# Power_Converter_Circuit.net
KiCad netlist of a schematic drawn in Altium Designer
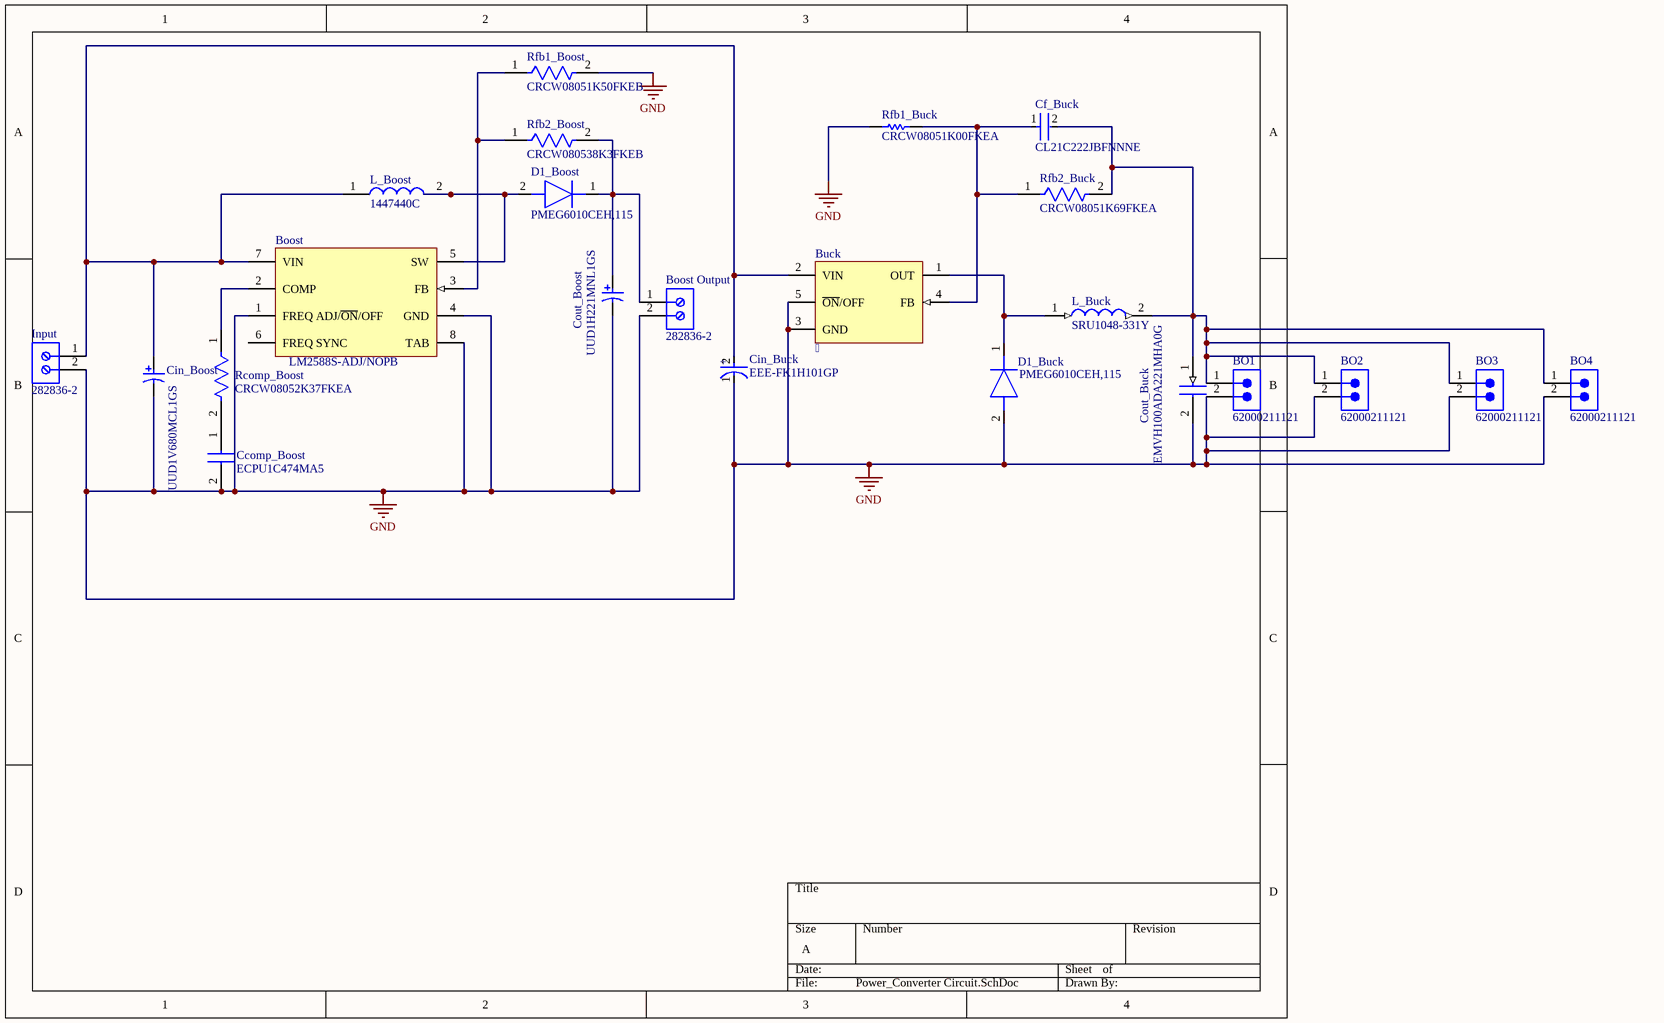
[diagram p0: Power_Converter Circuit.SchDoc]

(export (version "E")
  (design (tool "Eeschema 10.0.6"))
  (components
    (comp (ref "BO1")
      (value "62000211121")
      (footprint "62000211121")
      (libsource (lib "Altium Content Vault") (part "Header_Male_1R_02P"))
    )
    (comp (ref "BO2")
      (value "62000211121")
      (footprint "62000211121")
      (libsource (lib "Altium Content Vault") (part "Header_Male_1R_02P"))
    )
    (comp (ref "BO3")
      (value "62000211121")
      (footprint "62000211121")
      (libsource (lib "Altium Content Vault") (part "Header_Male_1R_02P"))
    )
    (comp (ref "BO4")
      (value "62000211121")
      (footprint "62000211121")
      (libsource (lib "Altium Content Vault") (part "Header_Male_1R_02P"))
    )
    (comp (ref "Boost")
      (value "LM2588S-ADJ/NOPB")
      (footprint "KTW0007B_N")
      (description "SIMPLE SWITCHER® 5A Flyback Regulator with Shutdown, 7-pin TO-263, Pb-Free")
      (fields (field (name "MANUFACTURER") "Texas Instruments"))
      (libsource (lib "Altium Content Vault") (part "PM-SWREG-LM2586S-12"))
    )
    (comp (ref "Boost Output")
      (value "282836-2")
      (footprint "TECO-282836-2_V")
      (description "Female Header, Pitch 5 mm, 1 x 2 Position, Height 10 mm, Tail Length 3.5 mm, Rohs, Bulk")
      (fields (field (name "VOLTAGE") "300V") (field (name "MANUFACTURER") "TE Connectivity"))
      (libsource (lib "Altium Content Vault") (part "CN-1P-F-TB2"))
    )
    (comp (ref "Buck")
      (value "")
      (footprint "NDH0005A")
      (description "SIMPLE SWITCHER® Power Converter 150 KHz 1A Step-Down Voltage Regulator, 5-pin TO-220, Pb-Free")
      (fields (field (name "MANUFACTURER") "Texas Instruments"))
      (libsource (lib "Altium Content Vault") (part "PM-REG-LM2595T-12"))
    )
    (comp (ref "Ccomp_Boost")
      (value "ECPU1C474MA5")
      (footprint "SamacSys:ECPU1C154MA5")
      (description "Capacitor")
      (libsource (lib "*") (part "ECPU1C474MA5"))
    )
    (comp (ref "Cf_Buck")
      (value "CL21C222JBFNNNE")
      (footprint "FP-CL21-IPC_C")
      (description "CL21 Series 0805 2.2nF 50V ±5% Tolerance C0G Multilayer Ceramic Chip Capacitor")
      (fields (field (name "TOLERANCE") "5%") (field (name "VOLTAGE") "50V"))
      (libsource (lib "Altium Content Vault") (part "b4654b650e69147ec39a6b967a45e02"))
    )
    (comp (ref "Cin_Boost")
      (value "UUD1V680MCL1GS")
      (footprint "NIC-CAPA2-6.3X7.7_V")
      (fields (field (name "MANUFACTURER") "Nichicon"))
      (libsource (lib "Altium Content Vault") (part "NIC-CAP-P-2"))
    )
    (comp (ref "Cin_Buck")
      (value "EEE-FK1H101GP")
      (footprint "FP-FKF-MFG")
      (description "CAP ALUM 100UF 20% 50V SMD")
      (fields (field (name "VOLTAGE") "50V") (field (name "TOLERANCE") "20%"))
      (libsource (lib "Altium Content Vault") (part "203bc49f2ac43e59fd269a8c329ed05"))
    )
    (comp (ref "Cout_Boost")
      (value "UUD1H221MNL1GS")
      (footprint "NIC-CAPA2-10X10_V")
      (fields (field (name "MANUFACTURER") "Nichicon"))
      (libsource (lib "Altium Content Vault") (part "NIC-CAP-P-2"))
    )
    (comp (ref "Cout_Buck")
      (value "EMVH100ADA221MHA0G")
      (footprint "SamacSys:CAPAE830X1050N")
      (description "Capacitor")
      (libsource (lib "*") (part "EMVH100ADA221MHA0G"))
    )
    (comp (ref "D1_Boost")
      (value "PMEG6010CEH,115")
      (footprint "SamacSys:SODFL3516X120N")
      (description "Diode")
      (fields (field (name "MOUSER PART NUMBER") "771-PMEG6010CEH-T/R"))
      (libsource (lib "*") (part "PMEG6010CEH,115"))
    )
    (comp (ref "D1_Buck")
      (value "PMEG6010CEH,115")
      (footprint "SamacSys:SODFL3516X120N")
      (description "Diode")
      (fields (field (name "MOUSER PART NUMBER") "771-PMEG6010CEH-T/R"))
      (libsource (lib "*") (part "PMEG6010CEH,115"))
    )
    (comp (ref "Input")
      (value "282836-2")
      (footprint "TECO-282836-2_V")
      (description "Female Header, Pitch 5 mm, 1 x 2 Position, Height 10 mm, Tail Length 3.5 mm, Rohs, Bulk")
      (fields (field (name "VOLTAGE") "300V") (field (name "MANUFACTURER") "TE Connectivity"))
      (libsource (lib "Altium Content Vault") (part "CN-1P-F-TB2"))
    )
    (comp (ref "L_Boost")
      (value "1447440C")
      (footprint "SamacSys:1447440C")
      (description "Inductor")
      (fields (field (name "MOUSER PART NUMBER") "580-1447440C"))
      (libsource (lib "*") (part "1447440C"))
    )
    (comp (ref "L_Buck")
      (value "SRU1048-331Y")
      (footprint "SamacSys:INDPM100100X510N")
      (description "Inductor")
      (libsource (lib "*") (part "SRU1048-331Y"))
    )
    (comp (ref "Rcomp_Boost")
      (value "CRCW08052K37FKEA")
      (footprint "FP-CRCW0805-e3-IPC_C")
      (description "RES Thick Film, 2.37kΩ, 1%, 0.125W, 100ppm/°C, 0805")
      (fields (field (name "TOLERANCE") "1%"))
      (libsource (lib "Altium Content Vault") (part "1029c3af85768c4190bb7ad29bc67b5"))
    )
    (comp (ref "Rfb1_Boost")
      (value "CRCW08051K50FKEB")
      (footprint "FP-CRCW0805-e3-IPC_C")
      (description "RES Thick Film, 1.5kΩ, 1%, 0.125W, 100ppm/°C, 0805")
      (fields (field (name "TOLERANCE") "1%"))
      (libsource (lib "Altium Content Vault") (part "1029c3af85768c4190bb7ad29bc67b5"))
    )
    (comp (ref "Rfb1_Buck")
      (value "CRCW08051K00FKEA")
      (footprint "RESC2013X50X30NL20T20")
      (fields (field (name "MANUFACTURER") "Vishay Dale"))
      (libsource (lib "Altium Content Vault") (part "RES"))
    )
    (comp (ref "Rfb2_Boost")
      (value "CRCW080538K3FKEB")
      (footprint "FP-CRCW0805-e3-MFG")
      (description "RES Thick Film, 38.3kΩ, 1%, 0.125W, 100ppm/°C, 0805")
      (fields (field (name "TOLERANCE") "1%"))
      (libsource (lib "Altium Content Vault") (part "1029c3af85768c4190bb7ad29bc67b5"))
    )
    (comp (ref "Rfb2_Buck")
      (value "CRCW08051K69FKEA")
      (footprint "FP-CRCW0805-e3-IPC_A")
      (description "RES Thick Film, 1.69kΩ, 1%, 0.125W, 100ppm/°C, 0805")
      (fields (field (name "TOLERANCE") "1%"))
      (libsource (lib "Altium Content Vault") (part "1029c3af85768c4190bb7ad29bc67b5"))
    )
  )
  (nets
    (net (code "1") (name "GND") (class "Default")
      (node (ref "BO1") (pin "2") (pinfunction "2_2") (pintype "passive"))
      (node (ref "BO2") (pin "2") (pinfunction "2_2") (pintype "passive"))
      (node (ref "BO3") (pin "2") (pinfunction "2_2") (pintype "passive"))
      (node (ref "BO4") (pin "2") (pinfunction "2_2") (pintype "passive"))
      (node (ref "Boost") (pin "1") (pinfunction "FREQ_ADJ/~{ON}/OFF_1") (pintype "passive"))
      (node (ref "Boost") (pin "4") (pinfunction "GND_4") (pintype "power_in"))
      (node (ref "Boost") (pin "8") (pinfunction "TAB_8") (pintype "passive"))
      (node (ref "Boost Output") (pin "2") (pinfunction "2_2") (pintype "passive"))
      (node (ref "Buck") (pin "3") (pinfunction "GND_3") (pintype "power_in"))
      (node (ref "Buck") (pin "5") (pinfunction "~{ON}/OFF_5") (pintype "passive"))
      (node (ref "Ccomp_Boost") (pin "2") (pinfunction "2_2") (pintype "passive"))
      (node (ref "Cin_Boost") (pin "2") (pinfunction "2_2") (pintype "passive"))
      (node (ref "Cin_Buck") (pin "1") (pinfunction "C_1") (pintype "passive"))
      (node (ref "Cout_Boost") (pin "2") (pinfunction "2_2") (pintype "passive"))
      (node (ref "Cout_Buck") (pin "2") (pinfunction "-_2") (pintype "passive"))
      (node (ref "D1_Buck") (pin "2") (pinfunction "A_2") (pintype "passive"))
      (node (ref "Input") (pin "2") (pinfunction "2_2") (pintype "passive"))
      (node (ref "Rfb1_Boost") (pin "2") (pinfunction "2_2") (pintype "passive"))
      (node (ref "Rfb1_Buck") (pin "1") (pinfunction "1_1") (pintype "passive"))
    )
    (net (code "2") (name "Net-(Boost-COMP)") (class "Default")
      (node (ref "Boost") (pin "2") (pinfunction "COMP_2") (pintype "passive"))
      (node (ref "Rcomp_Boost") (pin "1") (pinfunction "1_1") (pintype "passive"))
    )
    (net (code "3") (name "Net-(Boost-FB)") (class "Default")
      (node (ref "Boost") (pin "3") (pinfunction "FB_3") (pintype "input"))
      (node (ref "Rfb1_Boost") (pin "1") (pinfunction "1_1") (pintype "passive"))
      (node (ref "Rfb2_Boost") (pin "1") (pinfunction "1_1") (pintype "passive"))
    )
    (net (code "4") (name "Net-(Boost-SW)") (class "Default")
      (node (ref "Boost") (pin "5") (pinfunction "SW_5") (pintype "power_in"))
      (node (ref "D1_Boost") (pin "2") (pinfunction "A_2") (pintype "passive"))
      (node (ref "L_Boost") (pin "2") (pinfunction "2_2") (pintype "passive"))
    )
    (net (code "5") (name "Net-(Boost-VIN)") (class "Default")
      (node (ref "Boost") (pin "7") (pinfunction "VIN_7") (pintype "power_in"))
      (node (ref "Buck") (pin "2") (pinfunction "VIN_2") (pintype "power_in"))
      (node (ref "Cin_Boost") (pin "1") (pinfunction "1_1") (pintype "passive"))
      (node (ref "Cin_Buck") (pin "2") (pinfunction "A_2") (pintype "passive"))
      (node (ref "Input") (pin "1") (pinfunction "1_1") (pintype "passive"))
      (node (ref "L_Boost") (pin "1") (pinfunction "1_1") (pintype "passive"))
    )
    (net (code "6") (name "Net-(Buck-FB)") (class "Default")
      (node (ref "Buck") (pin "4") (pinfunction "FB_4") (pintype "input"))
      (node (ref "Cf_Buck") (pin "1") (pinfunction "1_1") (pintype "passive"))
      (node (ref "Rfb1_Buck") (pin "2") (pinfunction "2_2") (pintype "passive"))
      (node (ref "Rfb2_Buck") (pin "1") (pinfunction "1_1") (pintype "passive"))
    )
    (net (code "7") (name "Net-(Buck-OUT)") (class "Default")
      (node (ref "Buck") (pin "1") (pinfunction "OUT_1") (pintype "power_in"))
      (node (ref "D1_Buck") (pin "1") (pinfunction "K_1") (pintype "passive"))
      (node (ref "L_Buck") (pin "1") (pinfunction "1_1") (pintype "input"))
    )
    (net (code "8") (name "Net-(Ccomp_Boost-Pad1)") (class "Default")
      (node (ref "Ccomp_Boost") (pin "1") (pinfunction "1_1") (pintype "passive"))
      (node (ref "Rcomp_Boost") (pin "2") (pinfunction "2_2") (pintype "passive"))
    )
    (net (code "9") (name "Net-(Cout_Buck-+)") (class "Default")
      (node (ref "BO1") (pin "1") (pinfunction "1_1") (pintype "passive"))
      (node (ref "BO2") (pin "1") (pinfunction "1_1") (pintype "passive"))
      (node (ref "BO3") (pin "1") (pinfunction "1_1") (pintype "passive"))
      (node (ref "BO4") (pin "1") (pinfunction "1_1") (pintype "passive"))
      (node (ref "Cf_Buck") (pin "2") (pinfunction "2_2") (pintype "passive"))
      (node (ref "Cout_Buck") (pin "1") (pinfunction "+_1") (pintype "input"))
      (node (ref "L_Buck") (pin "2") (pinfunction "2_2") (pintype "output"))
      (node (ref "Rfb2_Buck") (pin "2") (pinfunction "2_2") (pintype "passive"))
    )
    (net (code "10") (name "Net-(D1_Boost-K)") (class "Default")
      (node (ref "Boost Output") (pin "1") (pinfunction "1_1") (pintype "passive"))
      (node (ref "Cout_Boost") (pin "1") (pinfunction "1_1") (pintype "passive"))
      (node (ref "D1_Boost") (pin "1") (pinfunction "K_1") (pintype "passive"))
      (node (ref "Rfb2_Boost") (pin "2") (pinfunction "2_2") (pintype "passive"))
    )
    (net (code "11") (name "unconnected-(Boost-FREQ_SYNC-Pad6)") (class "Default")
      (node (ref "Boost") (pin "6") (pinfunction "FREQ_SYNC_6") (pintype "passive"))
    )
  )
)
